# kid-v2.net
KiCad netlist of a schematic drawn in EAGLE
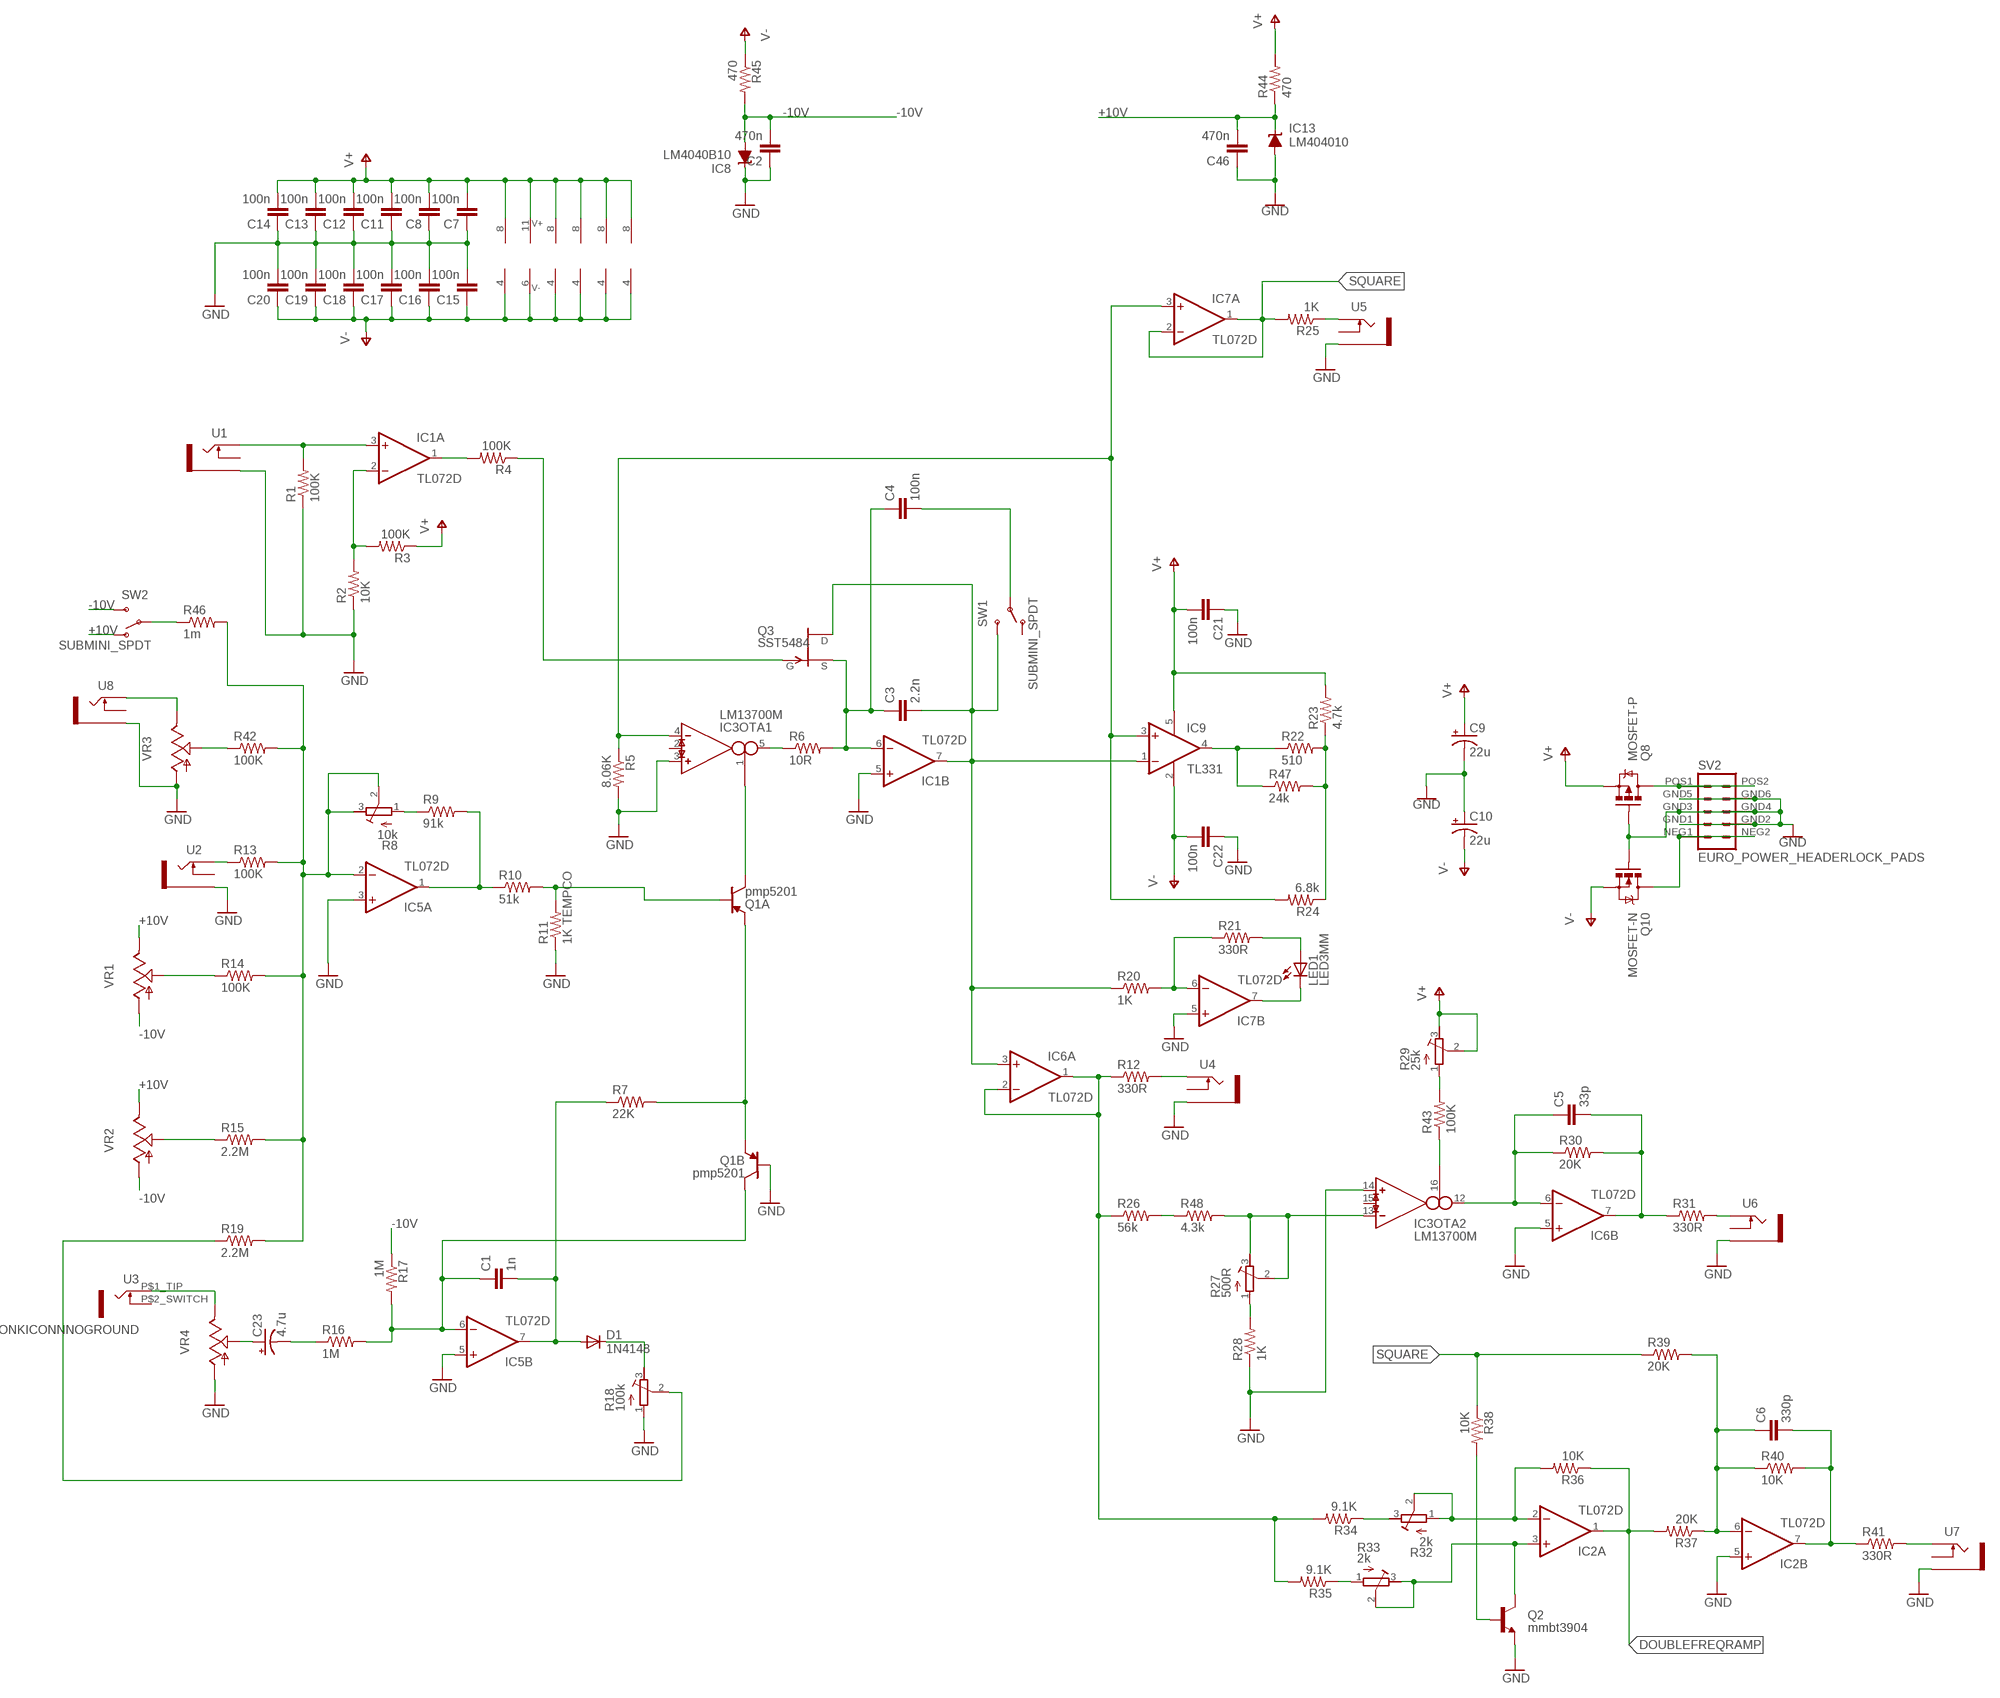
[diagram p0: schematic, sheet 1]

(export (version "E")
  (design (tool "Eeschema 10.0.6"))
  (components
    (comp (ref "C1")
      (value "1n")
      (footprint "eagle-import:C0603")
      (libsource (lib "eagle-import") (part "C-EUC0603"))
    )
    (comp (ref "C2")
      (value "470n")
      (footprint "eagle-import:0603-CAP")
      (libsource (lib "eagle-import") (part "CAP0603-CAP"))
    )
    (comp (ref "C3")
      (value "2.2n")
      (footprint "eagle-import:C0603")
      (libsource (lib "eagle-import") (part "C-EUC0603"))
    )
    (comp (ref "C4")
      (value "100n")
      (footprint "eagle-import:C0603")
      (libsource (lib "eagle-import") (part "C-EUC0603"))
    )
    (comp (ref "C5")
      (value "33p")
      (footprint "eagle-import:C0603")
      (libsource (lib "eagle-import") (part "C-EUC0603"))
    )
    (comp (ref "C6")
      (value "330p")
      (footprint "eagle-import:C0603")
      (libsource (lib "eagle-import") (part "C-EUC0603"))
    )
    (comp (ref "C7")
      (value "100n")
      (footprint "eagle-import:C0603")
      (libsource (lib "eagle-import") (part "C-EUC0603"))
    )
    (comp (ref "C8")
      (value "100n")
      (footprint "eagle-import:C0603")
      (libsource (lib "eagle-import") (part "C-EUC0603"))
    )
    (comp (ref "C9")
      (value "22u")
      (footprint "eagle-import:PANASONIC_C")
      (libsource (lib "eagle-import") (part "CPOL-USC"))
    )
    (comp (ref "C10")
      (value "22u")
      (footprint "eagle-import:PANASONIC_C")
      (libsource (lib "eagle-import") (part "CPOL-USC"))
    )
    (comp (ref "C11")
      (value "100n")
      (footprint "eagle-import:C0603")
      (libsource (lib "eagle-import") (part "C-EUC0603"))
    )
    (comp (ref "C12")
      (value "100n")
      (footprint "eagle-import:C0603")
      (libsource (lib "eagle-import") (part "C-EUC0603"))
    )
    (comp (ref "C13")
      (value "100n")
      (footprint "eagle-import:C0603")
      (libsource (lib "eagle-import") (part "C-EUC0603"))
    )
    (comp (ref "C14")
      (value "100n")
      (footprint "eagle-import:C0603")
      (libsource (lib "eagle-import") (part "C-EUC0603"))
    )
    (comp (ref "C15")
      (value "100n")
      (footprint "eagle-import:C0603")
      (libsource (lib "eagle-import") (part "C-EUC0603"))
    )
    (comp (ref "C16")
      (value "100n")
      (footprint "eagle-import:C0603")
      (libsource (lib "eagle-import") (part "C-EUC0603"))
    )
    (comp (ref "C17")
      (value "100n")
      (footprint "eagle-import:C0603")
      (libsource (lib "eagle-import") (part "C-EUC0603"))
    )
    (comp (ref "C18")
      (value "100n")
      (footprint "eagle-import:C0603")
      (libsource (lib "eagle-import") (part "C-EUC0603"))
    )
    (comp (ref "C19")
      (value "100n")
      (footprint "eagle-import:C0603")
      (libsource (lib "eagle-import") (part "C-EUC0603"))
    )
    (comp (ref "C20")
      (value "100n")
      (footprint "eagle-import:C0603")
      (libsource (lib "eagle-import") (part "C-EUC0603"))
    )
    (comp (ref "C21")
      (value "100n")
      (footprint "eagle-import:C0603")
      (libsource (lib "eagle-import") (part "C-EUC0603"))
    )
    (comp (ref "C22")
      (value "100n")
      (footprint "eagle-import:C0603")
      (libsource (lib "eagle-import") (part "C-EUC0603"))
    )
    (comp (ref "C23")
      (value "4.7u")
      (footprint "eagle-import:PANASONIC_B")
      (libsource (lib "eagle-import") (part "CPOL-USB"))
    )
    (comp (ref "C46")
      (value "470n")
      (footprint "eagle-import:0603-CAP")
      (libsource (lib "eagle-import") (part "CAP0603-CAP"))
    )
    (comp (ref "D1")
      (value "1N4148")
      (footprint "eagle-import:SOD-323")
      (libsource (lib "eagle-import") (part "DIODESOD"))
    )
    (comp (ref "IC1")
      (value "TL072D")
      (footprint "eagle-import:SO08")
      (libsource (lib "eagle-import") (part "TL072D"))
    )
    (comp (ref "IC2")
      (value "TL072D")
      (footprint "eagle-import:SO08")
      (libsource (lib "eagle-import") (part "TL072D"))
    )
    (comp (ref "IC3")
      (value "LM13700M")
      (footprint "eagle-import:SO16")
      (libsource (lib "eagle-import") (part "LM13700M"))
    )
    (comp (ref "IC5")
      (value "TL072D")
      (footprint "eagle-import:SO08")
      (libsource (lib "eagle-import") (part "TL072D"))
    )
    (comp (ref "IC6")
      (value "TL072D")
      (footprint "eagle-import:SO08")
      (libsource (lib "eagle-import") (part "TL072D"))
    )
    (comp (ref "IC7")
      (value "TL072D")
      (footprint "eagle-import:SO08")
      (libsource (lib "eagle-import") (part "TL072D"))
    )
    (comp (ref "IC8")
      (value "LM4040B10")
      (footprint "eagle-import:DBZ_R-PDSO-G3")
      (libsource (lib "eagle-import") (part "LM4041DBZB12"))
    )
    (comp (ref "IC9")
      (value "TL331")
      (footprint "eagle-import:DBV-R-PDSO-G5")
      (libsource (lib "eagle-import") (part "TL331"))
    )
    (comp (ref "IC13")
      (value "LM404010")
      (footprint "eagle-import:DBZ_R-PDSO-G3")
      (fields (field (name "MF") "TEXAS INSTRUMENT CONNECTORS") (field (name "MPN") "LM4041D12QDBZT"))
      (libsource (lib "eagle-import") (part "texas_387_LM4041DBZD12"))
    )
    (comp (ref "LED1")
      (value "LED3MM")
      (footprint "eagle-import:LED3MM")
      (libsource (lib "eagle-import") (part "LED3MM"))
    )
    (comp (ref "Q1")
      (value "pmp5201")
      (footprint "eagle-import:SOT363")
      (libsource (lib "eagle-import") (part "PNP-DUALPMP5201"))
    )
    (comp (ref "Q2")
      (value "mmbt3904")
      (footprint "eagle-import:SOT23")
      (libsource (lib "eagle-import") (part "TRANSISTOR_NPNSOT23"))
    )
    (comp (ref "Q3")
      (value "SST5484")
      (footprint "eagle-import:SOT23")
      (libsource (lib "eagle-import") (part "?548SST4"))
    )
    (comp (ref "Q8")
      (value "MOSFET-P")
      (footprint "eagle-import:SOT23-3")
      (libsource (lib "eagle-import") (part "MOSFET-P"))
    )
    (comp (ref "Q10")
      (value "MOSFET-N")
      (footprint "eagle-import:SOT23-3")
      (libsource (lib "eagle-import") (part "MOSFET-N"))
    )
    (comp (ref "R1")
      (value "100K")
      (footprint "eagle-import:R0603")
      (libsource (lib "eagle-import") (part "rcl_334_R-US_R0603"))
    )
    (comp (ref "R2")
      (value "10K")
      (footprint "eagle-import:R0603")
      (libsource (lib "eagle-import") (part "rcl_334_R-US_R0603"))
    )
    (comp (ref "R3")
      (value "100K")
      (footprint "eagle-import:R0603")
      (libsource (lib "eagle-import") (part "rcl_334_R-US_R0603"))
    )
    (comp (ref "R4")
      (value "100K")
      (footprint "eagle-import:R0603")
      (libsource (lib "eagle-import") (part "rcl_334_R-US_R0603"))
    )
    (comp (ref "R5")
      (value "8.06K")
      (footprint "eagle-import:R0603")
      (libsource (lib "eagle-import") (part "rcl_334_R-US_R0603"))
    )
    (comp (ref "R6")
      (value "10R")
      (footprint "eagle-import:R0603")
      (libsource (lib "eagle-import") (part "rcl_334_R-US_R0603"))
    )
    (comp (ref "R7")
      (value "22K")
      (footprint "eagle-import:R0603")
      (libsource (lib "eagle-import") (part "rcl_334_R-US_R0603"))
    )
    (comp (ref "R8")
      (value "10k")
      (footprint "eagle-import:RTRIM3296W")
      (libsource (lib "eagle-import") (part "R-TRIMM3296W"))
    )
    (comp (ref "R9")
      (value "91k")
      (footprint "eagle-import:R0603")
      (libsource (lib "eagle-import") (part "rcl_334_R-US_R0603"))
    )
    (comp (ref "R10")
      (value "51k")
      (footprint "eagle-import:R0603")
      (libsource (lib "eagle-import") (part "rcl_334_R-US_R0603"))
    )
    (comp (ref "R11")
      (value "1K TEMPCO")
      (footprint "eagle-import:R0805")
      (libsource (lib "eagle-import") (part "rcl_334_R-US_R0805"))
    )
    (comp (ref "R12")
      (value "330R")
      (footprint "eagle-import:R0603")
      (libsource (lib "eagle-import") (part "rcl_334_R-US_R0603"))
    )
    (comp (ref "R13")
      (value "100K")
      (footprint "eagle-import:R0603")
      (libsource (lib "eagle-import") (part "rcl_334_R-US_R0603"))
    )
    (comp (ref "R14")
      (value "100K")
      (footprint "eagle-import:R0603")
      (libsource (lib "eagle-import") (part "rcl_334_R-US_R0603"))
    )
    (comp (ref "R15")
      (value "2.2M")
      (footprint "eagle-import:R0603")
      (libsource (lib "eagle-import") (part "rcl_334_R-US_R0603"))
    )
    (comp (ref "R16")
      (value "1M")
      (footprint "eagle-import:R0603")
      (libsource (lib "eagle-import") (part "rcl_334_R-US_R0603"))
    )
    (comp (ref "R17")
      (value "1M")
      (footprint "eagle-import:R0603")
      (libsource (lib "eagle-import") (part "rcl_334_R-US_R0603"))
    )
    (comp (ref "R18")
      (value "100k")
      (footprint "eagle-import:RTRIM3296W")
      (libsource (lib "eagle-import") (part "R-TRIMM3296W"))
    )
    (comp (ref "R19")
      (value "2.2M")
      (footprint "eagle-import:R0603")
      (libsource (lib "eagle-import") (part "rcl_334_R-US_R0603"))
    )
    (comp (ref "R20")
      (value "1K")
      (footprint "eagle-import:R0603")
      (libsource (lib "eagle-import") (part "rcl_334_R-US_R0603"))
    )
    (comp (ref "R21")
      (value "330R")
      (footprint "eagle-import:R0603")
      (libsource (lib "eagle-import") (part "rcl_334_R-US_R0603"))
    )
    (comp (ref "R22")
      (value "510")
      (footprint "eagle-import:R0603")
      (libsource (lib "eagle-import") (part "rcl_334_R-US_R0603"))
    )
    (comp (ref "R23")
      (value "4.7k")
      (footprint "eagle-import:R0603")
      (libsource (lib "eagle-import") (part "rcl_334_R-US_R0603"))
    )
    (comp (ref "R24")
      (value "6.8k")
      (footprint "eagle-import:R0603")
      (libsource (lib "eagle-import") (part "rcl_334_R-US_R0603"))
    )
    (comp (ref "R25")
      (value "1K")
      (footprint "eagle-import:R0603")
      (libsource (lib "eagle-import") (part "rcl_334_R-US_R0603"))
    )
    (comp (ref "R26")
      (value "56k")
      (footprint "eagle-import:R0603")
      (libsource (lib "eagle-import") (part "rcl_334_R-US_R0603"))
    )
    (comp (ref "R27")
      (value "500R")
      (footprint "eagle-import:RTRIM3296W")
      (libsource (lib "eagle-import") (part "R-TRIMM3296W"))
    )
    (comp (ref "R28")
      (value "1K")
      (footprint "eagle-import:R0603")
      (libsource (lib "eagle-import") (part "rcl_334_R-US_R0603"))
    )
    (comp (ref "R29")
      (value "25k")
      (footprint "eagle-import:RTRIM3296W")
      (libsource (lib "eagle-import") (part "R-TRIMM3296W"))
    )
    (comp (ref "R30")
      (value "20K")
      (footprint "eagle-import:R0603")
      (libsource (lib "eagle-import") (part "rcl_334_R-US_R0603"))
    )
    (comp (ref "R31")
      (value "330R")
      (footprint "eagle-import:R0603")
      (libsource (lib "eagle-import") (part "rcl_334_R-US_R0603"))
    )
    (comp (ref "R32")
      (value "2k")
      (footprint "eagle-import:RTRIM3296W")
      (libsource (lib "eagle-import") (part "R-TRIMM3296W"))
    )
    (comp (ref "R33")
      (value "2k")
      (footprint "eagle-import:RTRIM3296W")
      (libsource (lib "eagle-import") (part "R-TRIMM3296W"))
    )
    (comp (ref "R34")
      (value "9.1K")
      (footprint "eagle-import:R0603")
      (libsource (lib "eagle-import") (part "rcl_334_R-US_R0603"))
    )
    (comp (ref "R35")
      (value "9.1K")
      (footprint "eagle-import:R0603")
      (libsource (lib "eagle-import") (part "rcl_334_R-US_R0603"))
    )
    (comp (ref "R36")
      (value "10K")
      (footprint "eagle-import:R0603")
      (libsource (lib "eagle-import") (part "rcl_334_R-US_R0603"))
    )
    (comp (ref "R37")
      (value "20K")
      (footprint "eagle-import:R0603")
      (libsource (lib "eagle-import") (part "rcl_334_R-US_R0603"))
    )
    (comp (ref "R38")
      (value "10K")
      (footprint "eagle-import:R0603")
      (libsource (lib "eagle-import") (part "rcl_334_R-US_R0603"))
    )
    (comp (ref "R39")
      (value "20K")
      (footprint "eagle-import:R0603")
      (libsource (lib "eagle-import") (part "rcl_334_R-US_R0603"))
    )
    (comp (ref "R40")
      (value "10K")
      (footprint "eagle-import:R0603")
      (libsource (lib "eagle-import") (part "rcl_334_R-US_R0603"))
    )
    (comp (ref "R41")
      (value "330R")
      (footprint "eagle-import:R0603")
      (libsource (lib "eagle-import") (part "rcl_334_R-US_R0603"))
    )
    (comp (ref "R42")
      (value "100K")
      (footprint "eagle-import:R0603")
      (libsource (lib "eagle-import") (part "rcl_334_R-US_R0603"))
    )
    (comp (ref "R43")
      (value "100K")
      (footprint "eagle-import:R0603")
      (libsource (lib "eagle-import") (part "rcl_334_R-US_R0603"))
    )
    (comp (ref "R44")
      (value "470")
      (footprint "eagle-import:0603-RES")
      (libsource (lib "eagle-import") (part "RESISTOR0603-RES"))
    )
    (comp (ref "R45")
      (value "470")
      (footprint "eagle-import:R0603")
      (libsource (lib "eagle-import") (part "R-US_R0603"))
    )
    (comp (ref "R46")
      (value "1m")
      (footprint "eagle-import:R0603")
      (libsource (lib "eagle-import") (part "rcl_334_R-US_R0603"))
    )
    (comp (ref "R47")
      (value "24k")
      (footprint "eagle-import:R0603")
      (libsource (lib "eagle-import") (part "rcl_334_R-US_R0603"))
    )
    (comp (ref "R48")
      (value "4.3k")
      (footprint "eagle-import:R0603")
      (libsource (lib "eagle-import") (part "rcl_334_R-US_R0603"))
    )
    (comp (ref "SV2")
      (value "EURO_POWER_HEADERLOCK_PADS")
      (footprint "eagle-import:EURO_PWR_HEADER_LOCK")
      (libsource (lib "eagle-import") (part "EURO_POWER_HEADERLOCK_PADS"))
    )
    (comp (ref "SW1")
      (value "SUBMINI_SPDT")
      (footprint "eagle-import:SUBMINI_TOGGLE")
      (libsource (lib "eagle-import") (part "SUBMINI_SPDT"))
    )
    (comp (ref "SW2")
      (value "SUBMINI_SPDT")
      (footprint "eagle-import:SUBMINI_TOGGLE")
      (libsource (lib "eagle-import") (part "SUBMINI_SPDT"))
    )
    (comp (ref "U1")
      (value "THONKICONNNEW")
      (footprint "eagle-import:WQP-PJ301M-12_JACK")
      (libsource (lib "eagle-import") (part "THONKICONNNEW"))
    )
    (comp (ref "U2")
      (value "THONKICONNNEW")
      (footprint "eagle-import:WQP-PJ301M-12_JACK")
      (libsource (lib "eagle-import") (part "THONKICONNNEW"))
    )
    (comp (ref "U3")
      (value "THONKICONNNOGROUND")
      (footprint "eagle-import:THONKICONNNOGROUND")
      (libsource (lib "eagle-import") (part "THONKICONNNOGROUND"))
    )
    (comp (ref "U4")
      (value "THONKICONNNEW")
      (footprint "eagle-import:WQP-PJ301M-12_JACK")
      (libsource (lib "eagle-import") (part "THONKICONNNEW"))
    )
    (comp (ref "U5")
      (value "THONKICONNNEW")
      (footprint "eagle-import:WQP-PJ301M-12_JACK")
      (libsource (lib "eagle-import") (part "THONKICONNNEW"))
    )
    (comp (ref "U6")
      (value "THONKICONNNEW")
      (footprint "eagle-import:WQP-PJ301M-12_JACK")
      (libsource (lib "eagle-import") (part "THONKICONNNEW"))
    )
    (comp (ref "U7")
      (value "THONKICONNNEW")
      (footprint "eagle-import:WQP-PJ301M-12_JACK")
      (libsource (lib "eagle-import") (part "THONKICONNNEW"))
    )
    (comp (ref "U8")
      (value "THONKICONNNEW")
      (footprint "eagle-import:WQP-PJ301M-12_JACK")
      (libsource (lib "eagle-import") (part "THONKICONNNEW"))
    )
    (comp (ref "VR1")
      (value "9MM_SNAP-IN_POT_")
      (footprint "eagle-import:9MM_SNAP-IN_POT")
      (libsource (lib "eagle-import") (part "9MM_SNAP-IN_POT_"))
    )
    (comp (ref "VR2")
      (value "9MM_SNAP-IN_POT_")
      (footprint "eagle-import:9MM_SNAP-IN_POT")
      (libsource (lib "eagle-import") (part "9MM_SNAP-IN_POT_"))
    )
    (comp (ref "VR3")
      (value "9MM_SNAP-IN_POT_")
      (footprint "eagle-import:9MM_SNAP-IN_POT")
      (libsource (lib "eagle-import") (part "9MM_SNAP-IN_POT_"))
    )
    (comp (ref "VR4")
      (value "9MM_SNAP-IN_POT_")
      (footprint "eagle-import:9MM_SNAP-IN_POT")
      (libsource (lib "eagle-import") (part "9MM_SNAP-IN_POT_"))
    )
  )
  (nets
    (net (code "1") (name "/+10V") (class "Default")
      (node (ref "C46") (pin "2") (pinfunction "2_2") (pintype "passive"))
      (node (ref "IC13") (pin "1") (pinfunction "C_1") (pintype "passive"))
      (node (ref "R44") (pin "1") (pinfunction "1_1") (pintype "passive"))
      (node (ref "SW2") (pin "1") (pinfunction "O_1") (pintype "passive"))
      (node (ref "VR1") (pin "3") (pinfunction "E_3") (pintype "passive"))
      (node (ref "VR2") (pin "3") (pinfunction "E_3") (pintype "passive"))
    )
    (net (code "2") (name "/-10V") (class "Default")
      (node (ref "C2") (pin "2") (pinfunction "2_2") (pintype "passive"))
      (node (ref "IC8") (pin "2") (pinfunction "A_2") (pintype "passive"))
      (node (ref "R17") (pin "1") (pinfunction "1_1") (pintype "passive"))
      (node (ref "R45") (pin "2") (pinfunction "2_2") (pintype "passive"))
      (node (ref "SW2") (pin "3") (pinfunction "S_3") (pintype "passive"))
      (node (ref "VR1") (pin "1") (pinfunction "A_1") (pintype "passive"))
      (node (ref "VR2") (pin "1") (pinfunction "A_1") (pintype "passive"))
    )
    (net (code "3") (name "DOUBLEFREQRAMP") (class "Default")
      (node (ref "IC2") (pin "1") (pinfunction "OUT_1") (pintype "output"))
      (node (ref "R36") (pin "1") (pinfunction "1_1") (pintype "passive"))
      (node (ref "R37") (pin "2") (pinfunction "2_2") (pintype "passive"))
    )
    (net (code "4") (name "GND") (class "Default")
      (node (ref "C10") (pin "+") (pinfunction "+_+") (pintype "passive"))
      (node (ref "C11") (pin "1") (pinfunction "1_1") (pintype "passive"))
      (node (ref "C12") (pin "1") (pinfunction "1_1") (pintype "passive"))
      (node (ref "C13") (pin "1") (pinfunction "1_1") (pintype "passive"))
      (node (ref "C14") (pin "1") (pinfunction "1_1") (pintype "passive"))
      (node (ref "C15") (pin "2") (pinfunction "2_2") (pintype "passive"))
      (node (ref "C16") (pin "2") (pinfunction "2_2") (pintype "passive"))
      (node (ref "C17") (pin "2") (pinfunction "2_2") (pintype "passive"))
      (node (ref "C18") (pin "2") (pinfunction "2_2") (pintype "passive"))
      (node (ref "C19") (pin "2") (pinfunction "2_2") (pintype "passive"))
      (node (ref "C2") (pin "1") (pinfunction "1_1") (pintype "passive"))
      (node (ref "C20") (pin "2") (pinfunction "2_2") (pintype "passive"))
      (node (ref "C21") (pin "1") (pinfunction "1_1") (pintype "passive"))
      (node (ref "C22") (pin "1") (pinfunction "1_1") (pintype "passive"))
      (node (ref "C46") (pin "1") (pinfunction "1_1") (pintype "passive"))
      (node (ref "C7") (pin "1") (pinfunction "1_1") (pintype "passive"))
      (node (ref "C8") (pin "1") (pinfunction "1_1") (pintype "passive"))
      (node (ref "C9") (pin "-") (pinfunction "-_-") (pintype "passive"))
      (node (ref "IC1") (pin "5") (pinfunction "+IN_5") (pintype "input"))
      (node (ref "IC13") (pin "2") (pinfunction "A_2") (pintype "passive"))
      (node (ref "IC2") (pin "5") (pinfunction "+IN_5") (pintype "input"))
      (node (ref "IC3") (pin "14") (pinfunction "IN_P_14") (pintype "input"))
      (node (ref "IC3") (pin "3") (pinfunction "IN_P_3") (pintype "input"))
      (node (ref "IC5") (pin "3") (pinfunction "+IN_3") (pintype "input"))
      (node (ref "IC5") (pin "5") (pinfunction "+IN_5") (pintype "input"))
      (node (ref "IC6") (pin "5") (pinfunction "+IN_5") (pintype "input"))
      (node (ref "IC7") (pin "5") (pinfunction "+IN_5") (pintype "input"))
      (node (ref "IC8") (pin "1") (pinfunction "C_1") (pintype "passive"))
      (node (ref "Q1") (pin "P$2") (pinfunction "B_P$2") (pintype "bidirectional"))
      (node (ref "Q10") (pin "1") (pinfunction "G_1") (pintype "passive"))
      (node (ref "Q2") (pin "2") (pinfunction "E_2") (pintype "passive"))
      (node (ref "Q8") (pin "1") (pinfunction "G_1") (pintype "passive"))
      (node (ref "R1") (pin "1") (pinfunction "1_1") (pintype "passive"))
      (node (ref "R11") (pin "1") (pinfunction "1_1") (pintype "passive"))
      (node (ref "R18") (pin "1") (pinfunction "A_1") (pintype "passive"))
      (node (ref "R2") (pin "1") (pinfunction "1_1") (pintype "passive"))
      (node (ref "R28") (pin "1") (pinfunction "1_1") (pintype "passive"))
      (node (ref "R5") (pin "2") (pinfunction "2_2") (pintype "passive"))
      (node (ref "SV2") (pin "GND1") (pinfunction "4_GND1") (pintype "passive"))
      (node (ref "SV2") (pin "GND2") (pinfunction "3_GND2") (pintype "passive"))
      (node (ref "SV2") (pin "GND3") (pinfunction "6_GND3") (pintype "passive"))
      (node (ref "SV2") (pin "GND4") (pinfunction "5_GND4") (pintype "passive"))
      (node (ref "SV2") (pin "GND5") (pinfunction "8_GND5") (pintype "passive"))
      (node (ref "SV2") (pin "GND6") (pinfunction "7_GND6") (pintype "passive"))
      (node (ref "U1") (pin "P$3_SLEEVE") (pinfunction "SLEEVE_P$3_SLEEVE") (pintype "passive"))
      (node (ref "U2") (pin "P$3_SLEEVE") (pinfunction "SLEEVE_P$3_SLEEVE") (pintype "passive"))
      (node (ref "U4") (pin "P$3_SLEEVE") (pinfunction "SLEEVE_P$3_SLEEVE") (pintype "passive"))
      (node (ref "U5") (pin "P$3_SLEEVE") (pinfunction "SLEEVE_P$3_SLEEVE") (pintype "passive"))
      (node (ref "U6") (pin "P$3_SLEEVE") (pinfunction "SLEEVE_P$3_SLEEVE") (pintype "passive"))
      (node (ref "U7") (pin "P$3_SLEEVE") (pinfunction "SLEEVE_P$3_SLEEVE") (pintype "passive"))
      (node (ref "U8") (pin "P$3_SLEEVE") (pinfunction "SLEEVE_P$3_SLEEVE") (pintype "passive"))
      (node (ref "VR3") (pin "1") (pinfunction "A_1") (pintype "passive"))
      (node (ref "VR4") (pin "1") (pinfunction "A_1") (pintype "passive"))
    )
    (net (code "5") (name "Net-(C23-Pad-)") (class "Default")
      (node (ref "C23") (pin "-") (pinfunction "-_-") (pintype "passive"))
      (node (ref "R16") (pin "1") (pinfunction "1_1") (pintype "passive"))
    )
    (net (code "6") (name "Net-(D1-A)") (class "Default")
      (node (ref "C1") (pin "2") (pinfunction "2_2") (pintype "passive"))
      (node (ref "D1") (pin "2") (pinfunction "A_2") (pintype "passive"))
      (node (ref "IC5") (pin "7") (pinfunction "OUT_7") (pintype "output"))
      (node (ref "R7") (pin "1") (pinfunction "1_1") (pintype "passive"))
    )
    (net (code "7") (name "Net-(D1-C)") (class "Default")
      (node (ref "D1") (pin "1") (pinfunction "C_1") (pintype "passive"))
      (node (ref "R18") (pin "3") (pinfunction "E_3") (pintype "passive"))
    )
    (net (code "8") (name "Net-(IC1A-+IN)") (class "Default")
      (node (ref "IC1") (pin "3") (pinfunction "+IN_3") (pintype "input"))
      (node (ref "R1") (pin "2") (pinfunction "2_2") (pintype "passive"))
      (node (ref "U1") (pin "P$1_TIP") (pinfunction "TIP_P$1_TIP") (pintype "passive"))
    )
    (net (code "9") (name "Net-(IC1A--IN)") (class "Default")
      (node (ref "IC1") (pin "2") (pinfunction "-IN_2") (pintype "input"))
      (node (ref "R2") (pin "2") (pinfunction "2_2") (pintype "passive"))
      (node (ref "R3") (pin "2") (pinfunction "2_2") (pintype "passive"))
    )
    (net (code "10") (name "Net-(IC1A-OUT)") (class "Default")
      (node (ref "IC1") (pin "1") (pinfunction "OUT_1") (pintype "output"))
      (node (ref "R4") (pin "2") (pinfunction "2_2") (pintype "passive"))
    )
    (net (code "11") (name "Net-(IC1B--IN)") (class "Default")
      (node (ref "C3") (pin "1") (pinfunction "1_1") (pintype "passive"))
      (node (ref "C4") (pin "1") (pinfunction "1_1") (pintype "passive"))
      (node (ref "IC1") (pin "6") (pinfunction "-IN_6") (pintype "input"))
      (node (ref "Q3") (pin "2") (pinfunction "S_2") (pintype "passive"))
      (node (ref "R6") (pin "2") (pinfunction "2_2") (pintype "passive"))
    )
    (net (code "12") (name "Net-(IC1B-OUT)") (class "Default")
      (node (ref "C3") (pin "2") (pinfunction "2_2") (pintype "passive"))
      (node (ref "IC1") (pin "7") (pinfunction "OUT_7") (pintype "output"))
      (node (ref "IC6") (pin "3") (pinfunction "+IN_3") (pintype "input"))
      (node (ref "IC9") (pin "1") (pinfunction "-IN_1") (pintype "input"))
      (node (ref "Q3") (pin "1") (pinfunction "D_1") (pintype "passive"))
      (node (ref "R20") (pin "1") (pinfunction "1_1") (pintype "passive"))
      (node (ref "SW1") (pin "3") (pinfunction "S_3") (pintype "passive"))
    )
    (net (code "13") (name "Net-(IC2A-+IN)") (class "Default")
      (node (ref "IC2") (pin "3") (pinfunction "+IN_3") (pintype "input"))
      (node (ref "Q2") (pin "3") (pinfunction "C_3") (pintype "passive"))
      (node (ref "R33") (pin "2") (pinfunction "S_2") (pintype "passive"))
      (node (ref "R33") (pin "3") (pinfunction "E_3") (pintype "passive"))
    )
    (net (code "14") (name "Net-(IC2A--IN)") (class "Default")
      (node (ref "IC2") (pin "2") (pinfunction "-IN_2") (pintype "input"))
      (node (ref "R32") (pin "1") (pinfunction "A_1") (pintype "passive"))
      (node (ref "R32") (pin "2") (pinfunction "S_2") (pintype "passive"))
      (node (ref "R36") (pin "2") (pinfunction "2_2") (pintype "passive"))
    )
    (net (code "15") (name "Net-(IC2B--IN)") (class "Default")
      (node (ref "C6") (pin "1") (pinfunction "1_1") (pintype "passive"))
      (node (ref "IC2") (pin "6") (pinfunction "-IN_6") (pintype "input"))
      (node (ref "R37") (pin "1") (pinfunction "1_1") (pintype "passive"))
      (node (ref "R39") (pin "2") (pinfunction "2_2") (pintype "passive"))
      (node (ref "R40") (pin "1") (pinfunction "1_1") (pintype "passive"))
    )
    (net (code "16") (name "Net-(IC2B-OUT)") (class "Default")
      (node (ref "C6") (pin "2") (pinfunction "2_2") (pintype "passive"))
      (node (ref "IC2") (pin "7") (pinfunction "OUT_7") (pintype "output"))
      (node (ref "R40") (pin "2") (pinfunction "2_2") (pintype "passive"))
      (node (ref "R41") (pin "1") (pinfunction "1_1") (pintype "passive"))
    )
    (net (code "17") (name "Net-(IC3C-IN_N)") (class "Default")
      (node (ref "IC3") (pin "4") (pinfunction "IN_N_4") (pintype "input"))
      (node (ref "IC7") (pin "3") (pinfunction "+IN_3") (pintype "input"))
      (node (ref "IC9") (pin "3") (pinfunction "+IN_3") (pintype "input"))
      (node (ref "R24") (pin "2") (pinfunction "2_2") (pintype "passive"))
      (node (ref "R5") (pin "1") (pinfunction "1_1") (pintype "passive"))
    )
    (net (code "18") (name "Net-(IC3C-I_BIAS)") (class "Default")
      (node (ref "IC3") (pin "1") (pinfunction "I_BIAS_1") (pintype "input"))
      (node (ref "Q1") (pin "P$6") (pinfunction "C_P$6") (pintype "bidirectional"))
    )
    (net (code "19") (name "Net-(IC3C-OUT)") (class "Default")
      (node (ref "IC3") (pin "5") (pinfunction "OUT_5") (pintype "output"))
      (node (ref "R6") (pin "1") (pinfunction "1_1") (pintype "passive"))
    )
    (net (code "20") (name "Net-(IC3D-IN_N)") (class "Default")
      (node (ref "IC3") (pin "13") (pinfunction "IN_N_13") (pintype "input"))
      (node (ref "R27") (pin "2") (pinfunction "S_2") (pintype "passive"))
      (node (ref "R27") (pin "3") (pinfunction "E_3") (pintype "passive"))
      (node (ref "R48") (pin "2") (pinfunction "2_2") (pintype "passive"))
    )
    (net (code "21") (name "Net-(IC3D-I_BIAS)") (class "Default")
      (node (ref "IC3") (pin "16") (pinfunction "I_BIAS_16") (pintype "input"))
      (node (ref "R43") (pin "1") (pinfunction "1_1") (pintype "passive"))
    )
    (net (code "22") (name "Net-(IC3D-OUT)") (class "Default")
      (node (ref "C5") (pin "1") (pinfunction "1_1") (pintype "passive"))
      (node (ref "IC3") (pin "12") (pinfunction "OUT_12") (pintype "output"))
      (node (ref "IC6") (pin "6") (pinfunction "-IN_6") (pintype "input"))
      (node (ref "R30") (pin "1") (pinfunction "1_1") (pintype "passive"))
    )
    (net (code "23") (name "Net-(IC5A--IN)") (class "Default")
      (node (ref "IC5") (pin "2") (pinfunction "-IN_2") (pintype "input"))
      (node (ref "R13") (pin "2") (pinfunction "2_2") (pintype "passive"))
      (node (ref "R14") (pin "2") (pinfunction "2_2") (pintype "passive"))
      (node (ref "R15") (pin "2") (pinfunction "2_2") (pintype "passive"))
      (node (ref "R19") (pin "2") (pinfunction "2_2") (pintype "passive"))
      (node (ref "R42") (pin "2") (pinfunction "2_2") (pintype "passive"))
      (node (ref "R46") (pin "2") (pinfunction "2_2") (pintype "passive"))
      (node (ref "R8") (pin "2") (pinfunction "S_2") (pintype "passive"))
      (node (ref "R8") (pin "3") (pinfunction "E_3") (pintype "passive"))
    )
    (net (code "24") (name "Net-(IC5A-OUT)") (class "Default")
      (node (ref "IC5") (pin "1") (pinfunction "OUT_1") (pintype "output"))
      (node (ref "R10") (pin "1") (pinfunction "1_1") (pintype "passive"))
      (node (ref "R9") (pin "2") (pinfunction "2_2") (pintype "passive"))
    )
    (net (code "25") (name "Net-(IC5B--IN)") (class "Default")
      (node (ref "C1") (pin "1") (pinfunction "1_1") (pintype "passive"))
      (node (ref "IC5") (pin "6") (pinfunction "-IN_6") (pintype "input"))
      (node (ref "Q1") (pin "P$3") (pinfunction "C_P$3") (pintype "bidirectional"))
      (node (ref "R16") (pin "2") (pinfunction "2_2") (pintype "passive"))
      (node (ref "R17") (pin "2") (pinfunction "2_2") (pintype "passive"))
    )
    (net (code "26") (name "Net-(IC6A--IN)") (class "Default")
      (node (ref "IC6") (pin "1") (pinfunction "OUT_1") (pintype "output"))
      (node (ref "IC6") (pin "2") (pinfunction "-IN_2") (pintype "input"))
      (node (ref "R12") (pin "1") (pinfunction "1_1") (pintype "passive"))
      (node (ref "R26") (pin "1") (pinfunction "1_1") (pintype "passive"))
      (node (ref "R34") (pin "2") (pinfunction "2_2") (pintype "passive"))
      (node (ref "R35") (pin "2") (pinfunction "2_2") (pintype "passive"))
    )
    (net (code "27") (name "Net-(IC6B-OUT)") (class "Default")
      (node (ref "C5") (pin "2") (pinfunction "2_2") (pintype "passive"))
      (node (ref "IC6") (pin "7") (pinfunction "OUT_7") (pintype "output"))
      (node (ref "R30") (pin "2") (pinfunction "2_2") (pintype "passive"))
      (node (ref "R31") (pin "1") (pinfunction "1_1") (pintype "passive"))
    )
    (net (code "28") (name "Net-(IC7B--IN)") (class "Default")
      (node (ref "IC7") (pin "6") (pinfunction "-IN_6") (pintype "input"))
      (node (ref "R20") (pin "2") (pinfunction "2_2") (pintype "passive"))
      (node (ref "R21") (pin "1") (pinfunction "1_1") (pintype "passive"))
    )
    (net (code "29") (name "Net-(IC7B-OUT)") (class "Default")
      (node (ref "IC7") (pin "7") (pinfunction "OUT_7") (pintype "output"))
      (node (ref "LED1") (pin "K") (pinfunction "C_K") (pintype "passive"))
    )
    (net (code "30") (name "Net-(IC9-OUT)") (class "Default")
      (node (ref "IC9") (pin "4") (pinfunction "OUT_4") (pintype "output"))
      (node (ref "R22") (pin "1") (pinfunction "1_1") (pintype "passive"))
      (node (ref "R47") (pin "1") (pinfunction "1_1") (pintype "passive"))
    )
    (net (code "31") (name "Net-(LED1-PadA)") (class "Default")
      (node (ref "LED1") (pin "A") (pinfunction "A_A") (pintype "passive"))
      (node (ref "R21") (pin "2") (pinfunction "2_2") (pintype "passive"))
    )
    (net (code "32") (name "Net-(Q1A-B)") (class "Default")
      (node (ref "Q1") (pin "P$1") (pinfunction "B_P$1") (pintype "bidirectional"))
      (node (ref "R10") (pin "2") (pinfunction "2_2") (pintype "passive"))
      (node (ref "R11") (pin "2") (pinfunction "2_2") (pintype "passive"))
    )
    (net (code "33") (name "Net-(Q1A-E)") (class "Default")
      (node (ref "Q1") (pin "P$4") (pinfunction "E_P$4") (pintype "bidirectional"))
      (node (ref "Q1") (pin "P$5") (pinfunction "E_P$5") (pintype "bidirectional"))
      (node (ref "R7") (pin "2") (pinfunction "2_2") (pintype "passive"))
    )
    (net (code "34") (name "Net-(Q2-B)") (class "Default")
      (node (ref "Q2") (pin "1") (pinfunction "B_1") (pintype "passive"))
      (node (ref "R38") (pin "2") (pinfunction "2_2") (pintype "passive"))
    )
    (net (code "35") (name "Net-(Q3-G)") (class "Default")
      (node (ref "Q3") (pin "3") (pinfunction "G_3") (pintype "passive"))
      (node (ref "R4") (pin "1") (pinfunction "1_1") (pintype "passive"))
    )
    (net (code "36") (name "Net-(Q8-D)") (class "Default")
      (node (ref "Q8") (pin "3") (pinfunction "D_3") (pintype "passive"))
      (node (ref "SV2") (pin "POS1") (pinfunction "10_POS1") (pintype "passive"))
      (node (ref "SV2") (pin "POS2") (pinfunction "9_POS2") (pintype "passive"))
    )
    (net (code "37") (name "Net-(Q10-D)") (class "Default")
      (node (ref "Q10") (pin "3") (pinfunction "D_3") (pintype "passive"))
      (node (ref "SV2") (pin "NEG1") (pinfunction "2_NEG1") (pintype "passive"))
      (node (ref "SV2") (pin "NEG2") (pinfunction "1_NEG2") (pintype "passive"))
    )
    (net (code "38") (name "Net-(R8-A)") (class "Default")
      (node (ref "R8") (pin "1") (pinfunction "A_1") (pintype "passive"))
      (node (ref "R9") (pin "1") (pinfunction "1_1") (pintype "passive"))
    )
    (net (code "39") (name "Net-(R18-S)") (class "Default")
      (node (ref "R18") (pin "2") (pinfunction "S_2") (pintype "passive"))
      (node (ref "R19") (pin "1") (pinfunction "1_1") (pintype "passive"))
    )
    (net (code "40") (name "Net-(R22-Pad2)") (class "Default")
      (node (ref "R22") (pin "2") (pinfunction "2_2") (pintype "passive"))
      (node (ref "R23") (pin "1") (pinfunction "1_1") (pintype "passive"))
      (node (ref "R24") (pin "1") (pinfunction "1_1") (pintype "passive"))
      (node (ref "R47") (pin "2") (pinfunction "2_2") (pintype "passive"))
    )
    (net (code "41") (name "Net-(R26-Pad2)") (class "Default")
      (node (ref "R26") (pin "2") (pinfunction "2_2") (pintype "passive"))
      (node (ref "R48") (pin "1") (pinfunction "1_1") (pintype "passive"))
    )
    (net (code "42") (name "Net-(R27-A)") (class "Default")
      (node (ref "R27") (pin "1") (pinfunction "A_1") (pintype "passive"))
      (node (ref "R28") (pin "2") (pinfunction "2_2") (pintype "passive"))
    )
    (net (code "43") (name "Net-(R29-A)") (class "Default")
      (node (ref "R29") (pin "1") (pinfunction "A_1") (pintype "passive"))
      (node (ref "R43") (pin "2") (pinfunction "2_2") (pintype "passive"))
    )
    (net (code "44") (name "Net-(R32-E)") (class "Default")
      (node (ref "R32") (pin "3") (pinfunction "E_3") (pintype "passive"))
      (node (ref "R34") (pin "1") (pinfunction "1_1") (pintype "passive"))
    )
    (net (code "45") (name "Net-(R33-A)") (class "Default")
      (node (ref "R33") (pin "1") (pinfunction "A_1") (pintype "passive"))
      (node (ref "R35") (pin "1") (pinfunction "1_1") (pintype "passive"))
    )
    (net (code "46") (name "Net-(SW1-COMMON)") (class "Default")
      (node (ref "C4") (pin "2") (pinfunction "2_2") (pintype "passive"))
      (node (ref "SW1") (pin "COM") (pinfunction "COMMON_COM") (pintype "passive"))
    )
    (net (code "47") (name "Net-(SW2-COMMON)") (class "Default")
      (node (ref "R46") (pin "1") (pinfunction "1_1") (pintype "passive"))
      (node (ref "SW2") (pin "COM") (pinfunction "COMMON_COM") (pintype "passive"))
    )
    (net (code "48") (name "Net-(U2-TIP)") (class "Default")
      (node (ref "R13") (pin "1") (pinfunction "1_1") (pintype "passive"))
      (node (ref "U2") (pin "P$1_TIP") (pinfunction "TIP_P$1_TIP") (pintype "passive"))
    )
    (net (code "49") (name "Net-(U3-2)") (class "Default")
      (node (ref "U3") (pin "P$1_TIP") (pinfunction "2_P$1_TIP") (pintype "passive"))
      (node (ref "VR4") (pin "3") (pinfunction "E_3") (pintype "passive"))
    )
    (net (code "50") (name "Net-(U4-TIP)") (class "Default")
      (node (ref "R12") (pin "2") (pinfunction "2_2") (pintype "passive"))
      (node (ref "U4") (pin "P$1_TIP") (pinfunction "TIP_P$1_TIP") (pintype "passive"))
    )
    (net (code "51") (name "Net-(U5-TIP)") (class "Default")
      (node (ref "R25") (pin "1") (pinfunction "1_1") (pintype "passive"))
      (node (ref "U5") (pin "P$1_TIP") (pinfunction "TIP_P$1_TIP") (pintype "passive"))
    )
    (net (code "52") (name "Net-(U6-TIP)") (class "Default")
      (node (ref "R31") (pin "2") (pinfunction "2_2") (pintype "passive"))
      (node (ref "U6") (pin "P$1_TIP") (pinfunction "TIP_P$1_TIP") (pintype "passive"))
    )
    (net (code "53") (name "Net-(U7-TIP)") (class "Default")
      (node (ref "R41") (pin "2") (pinfunction "2_2") (pintype "passive"))
      (node (ref "U7") (pin "P$1_TIP") (pinfunction "TIP_P$1_TIP") (pintype "passive"))
    )
    (net (code "54") (name "Net-(U8-TIP)") (class "Default")
      (node (ref "U8") (pin "P$1_TIP") (pinfunction "TIP_P$1_TIP") (pintype "passive"))
      (node (ref "VR3") (pin "3") (pinfunction "E_3") (pintype "passive"))
    )
    (net (code "55") (name "Net-(VR1-S)") (class "Default")
      (node (ref "R14") (pin "1") (pinfunction "1_1") (pintype "passive"))
      (node (ref "VR1") (pin "2") (pinfunction "S_2") (pintype "passive"))
    )
    (net (code "56") (name "Net-(VR2-S)") (class "Default")
      (node (ref "R15") (pin "1") (pinfunction "1_1") (pintype "passive"))
      (node (ref "VR2") (pin "2") (pinfunction "S_2") (pintype "passive"))
    )
    (net (code "57") (name "Net-(VR3-S)") (class "Default")
      (node (ref "R42") (pin "1") (pinfunction "1_1") (pintype "passive"))
      (node (ref "VR3") (pin "2") (pinfunction "S_2") (pintype "passive"))
    )
    (net (code "58") (name "Net-(VR4-S)") (class "Default")
      (node (ref "C23") (pin "+") (pinfunction "+_+") (pintype "passive"))
      (node (ref "VR4") (pin "2") (pinfunction "S_2") (pintype "passive"))
    )
    (net (code "59") (name "SQUARE") (class "Default")
      (node (ref "IC7") (pin "1") (pinfunction "OUT_1") (pintype "output"))
      (node (ref "IC7") (pin "2") (pinfunction "-IN_2") (pintype "input"))
      (node (ref "R25") (pin "2") (pinfunction "2_2") (pintype "passive"))
      (node (ref "R38") (pin "1") (pinfunction "1_1") (pintype "passive"))
      (node (ref "R39") (pin "1") (pinfunction "1_1") (pintype "passive"))
    )
    (net (code "60") (name "V+") (class "Default")
      (node (ref "C11") (pin "2") (pinfunction "2_2") (pintype "passive"))
      (node (ref "C12") (pin "2") (pinfunction "2_2") (pintype "passive"))
      (node (ref "C13") (pin "2") (pinfunction "2_2") (pintype "passive"))
      (node (ref "C14") (pin "2") (pinfunction "2_2") (pintype "passive"))
      (node (ref "C21") (pin "2") (pinfunction "2_2") (pintype "passive"))
      (node (ref "C7") (pin "2") (pinfunction "2_2") (pintype "passive"))
      (node (ref "C8") (pin "2") (pinfunction "2_2") (pintype "passive"))
      (node (ref "C9") (pin "+") (pinfunction "+_+") (pintype "passive"))
      (node (ref "IC1") (pin "8") (pinfunction "V+_8") (pintype "power_in"))
      (node (ref "IC2") (pin "8") (pinfunction "V+_8") (pintype "power_in"))
      (node (ref "IC3") (pin "11") (pinfunction "V+_11") (pintype "power_in"))
      (node (ref "IC5") (pin "8") (pinfunction "V+_8") (pintype "power_in"))
      (node (ref "IC6") (pin "8") (pinfunction "V+_8") (pintype "power_in"))
      (node (ref "IC7") (pin "8") (pinfunction "V+_8") (pintype "power_in"))
      (node (ref "IC9") (pin "5") (pinfunction "V+_5") (pintype "power_in"))
      (node (ref "Q8") (pin "2") (pinfunction "S_2") (pintype "passive"))
      (node (ref "R23") (pin "2") (pinfunction "2_2") (pintype "passive"))
      (node (ref "R29") (pin "2") (pinfunction "S_2") (pintype "passive"))
      (node (ref "R29") (pin "3") (pinfunction "E_3") (pintype "passive"))
      (node (ref "R3") (pin "1") (pinfunction "1_1") (pintype "passive"))
      (node (ref "R44") (pin "2") (pinfunction "2_2") (pintype "passive"))
    )
    (net (code "61") (name "V-") (class "Default")
      (node (ref "C10") (pin "-") (pinfunction "-_-") (pintype "passive"))
      (node (ref "C15") (pin "1") (pinfunction "1_1") (pintype "passive"))
      (node (ref "C16") (pin "1") (pinfunction "1_1") (pintype "passive"))
      (node (ref "C17") (pin "1") (pinfunction "1_1") (pintype "passive"))
      (node (ref "C18") (pin "1") (pinfunction "1_1") (pintype "passive"))
      (node (ref "C19") (pin "1") (pinfunction "1_1") (pintype "passive"))
      (node (ref "C20") (pin "1") (pinfunction "1_1") (pintype "passive"))
      (node (ref "C22") (pin "2") (pinfunction "2_2") (pintype "passive"))
      (node (ref "IC1") (pin "4") (pinfunction "V-_4") (pintype "power_in"))
      (node (ref "IC2") (pin "4") (pinfunction "V-_4") (pintype "power_in"))
      (node (ref "IC3") (pin "6") (pinfunction "V-_6") (pintype "power_in"))
      (node (ref "IC5") (pin "4") (pinfunction "V-_4") (pintype "power_in"))
      (node (ref "IC6") (pin "4") (pinfunction "V-_4") (pintype "power_in"))
      (node (ref "IC7") (pin "4") (pinfunction "V-_4") (pintype "power_in"))
      (node (ref "IC9") (pin "2") (pinfunction "GND_2") (pintype "power_in"))
      (node (ref "Q10") (pin "2") (pinfunction "S_2") (pintype "passive"))
      (node (ref "R45") (pin "1") (pinfunction "1_1") (pintype "passive"))
    )
    (net (code "62") (name "unconnected-(IC3C-I_DIODE-Pad2)") (class "Default")
      (node (ref "IC3") (pin "2") (pinfunction "I_DIODE_2") (pintype "input"))
    )
    (net (code "63") (name "unconnected-(IC3D-I_DIODE-Pad15)") (class "Default")
      (node (ref "IC3") (pin "15") (pinfunction "I_DIODE_15") (pintype "input"))
    )
    (net (code "64") (name "unconnected-(SW1-O-Pad1)") (class "Default")
      (node (ref "SW1") (pin "1") (pinfunction "O_1") (pintype "passive"))
    )
    (net (code "65") (name "unconnected-(U1-SWITCH-PadP$2_SWITCH)") (class "Default")
      (node (ref "U1") (pin "P$2_SWITCH") (pinfunction "SWITCH_P$2_SWITCH") (pintype "passive"))
    )
    (net (code "66") (name "unconnected-(U2-SWITCH-PadP$2_SWITCH)") (class "Default")
      (node (ref "U2") (pin "P$2_SWITCH") (pinfunction "SWITCH_P$2_SWITCH") (pintype "passive"))
    )
    (net (code "67") (name "unconnected-(U3-3-PadP$2_SWITCH)") (class "Default")
      (node (ref "U3") (pin "P$2_SWITCH") (pinfunction "3_P$2_SWITCH") (pintype "passive"))
    )
    (net (code "68") (name "unconnected-(U4-SWITCH-PadP$2_SWITCH)") (class "Default")
      (node (ref "U4") (pin "P$2_SWITCH") (pinfunction "SWITCH_P$2_SWITCH") (pintype "passive"))
    )
    (net (code "69") (name "unconnected-(U5-SWITCH-PadP$2_SWITCH)") (class "Default")
      (node (ref "U5") (pin "P$2_SWITCH") (pinfunction "SWITCH_P$2_SWITCH") (pintype "passive"))
    )
    (net (code "70") (name "unconnected-(U6-SWITCH-PadP$2_SWITCH)") (class "Default")
      (node (ref "U6") (pin "P$2_SWITCH") (pinfunction "SWITCH_P$2_SWITCH") (pintype "passive"))
    )
    (net (code "71") (name "unconnected-(U7-SWITCH-PadP$2_SWITCH)") (class "Default")
      (node (ref "U7") (pin "P$2_SWITCH") (pinfunction "SWITCH_P$2_SWITCH") (pintype "passive"))
    )
    (net (code "72") (name "unconnected-(U8-SWITCH-PadP$2_SWITCH)") (class "Default")
      (node (ref "U8") (pin "P$2_SWITCH") (pinfunction "SWITCH_P$2_SWITCH") (pintype "passive"))
    )
  )
)
